# 07_Audio.net
KiCad netlist of a schematic drawn in Altium Designer
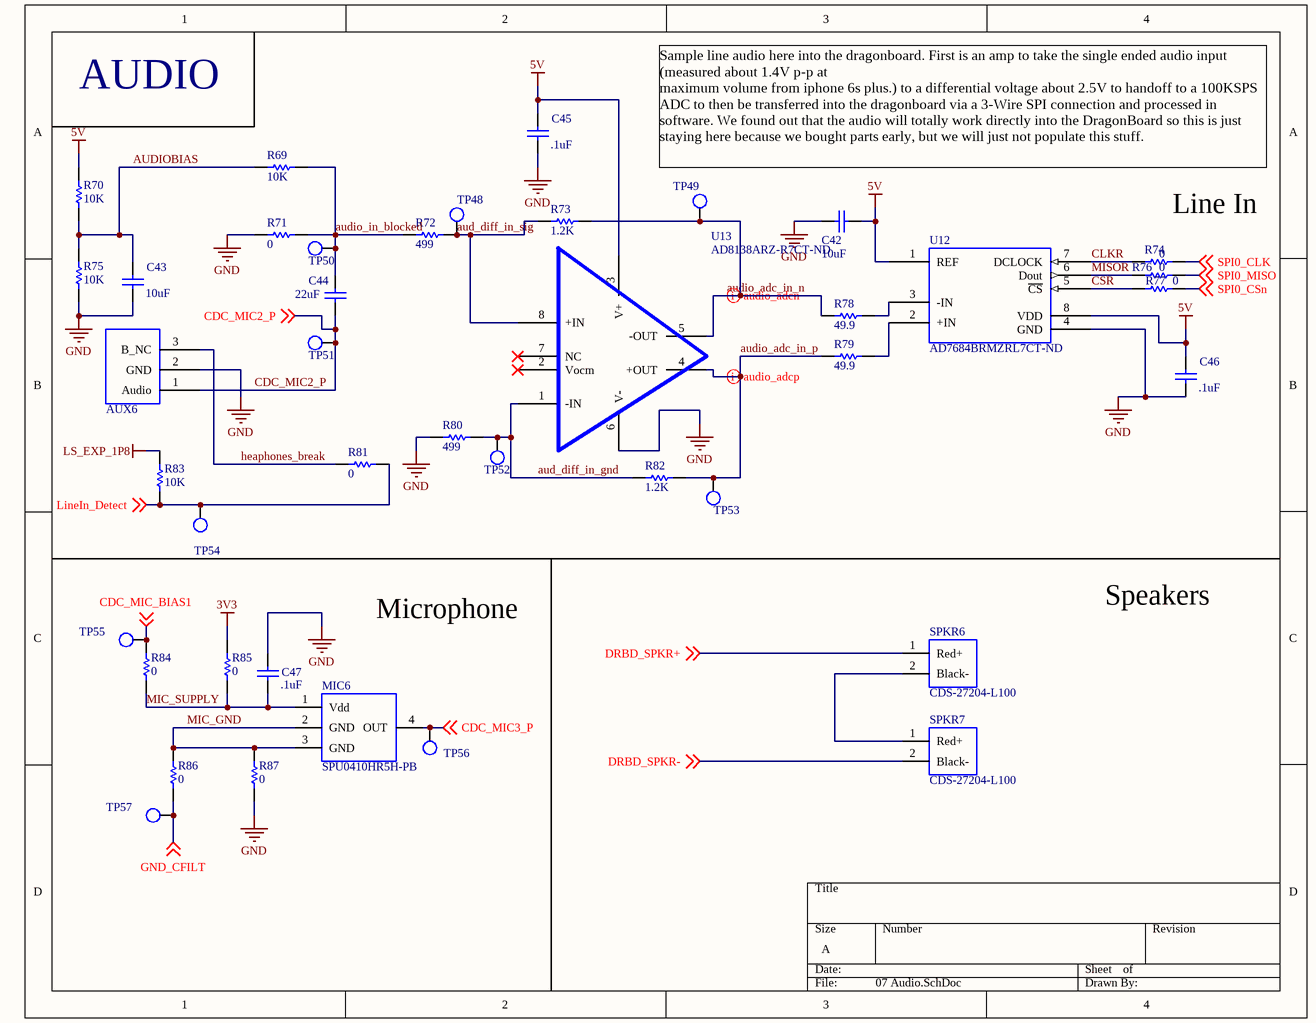
[diagram p0: 07 Audio.SchDoc]

(export (version "E")
  (design (tool "Eeschema 10.0.6"))
  (components
    (comp (ref "AUX6")
      (value "CP-3523MJCT-ND")
      (footprint "Audio_Conn_Mono")
      (description "3.50mm (0.141\", 1/8\", Mini Plug) - Headphone Phone Jack Mono Connector Solder")
      (fields (field (name "MANUFACTURER") "CUI") (field (name "MANUFACTURER PART NUMBER") "MJ-3523-SMT-TR"))
      (libsource (lib "schlib_truman") (part "CP-3523MJCT-ND"))
    )
    (comp (ref "C42")
      (value "10uF")
      (footprint "CAPC2012X135N")
      (description "Cap Ceramic 10uF 16V X5R 10% SMD 0805 85C T/R")
      (fields
        (field (name "MANUFACTURER") "Johanson Dielectrics")
        (field (name "MANUFACTURER PART NUMBER") "160R15X106KV4E")
      )
      (libsource (lib "schlib_truman") (part "CAP_0805_10u_16V"))
    )
    (comp (ref "C43")
      (value "10uF")
      (footprint "CAPC2012X135N")
      (description "Cap Ceramic 10uF 16V X5R 10% SMD 0805 85C T/R")
      (fields
        (field (name "MANUFACTURER") "Johanson Dielectrics")
        (field (name "MANUFACTURER PART NUMBER") "160R15X106KV4E")
      )
      (libsource (lib "schlib_truman") (part "CAP_0805_10u_16V"))
    )
    (comp (ref "C44")
      (value "22uF")
      (footprint "CAPC2012X135N")
      (fields
        (field (name "MANUFACTURER") "Samsung")
        (field (name "MANUFACTURER PART NUMBER") "CL21A226MAQNNNE")
        (field (name "TOLERANCE") "20%")
      )
      (libsource (lib "schlib_truman") (part "CAP_0805_22u_25V_BLOCK"))
    )
    (comp (ref "C45")
      (value ".1uF")
      (footprint "CAPC2012X135N")
      (description "Cap Ceramic 0.1uF 250V X7T 10% SMD 0805 125C Plastic T/R")
      (fields
        (field (name "MANUFACTURER") "TDK")
        (field (name "MANUFACTURER PART NUMBER") "C2012X7T2E104K125AE")
      )
      (libsource (lib "schlib_truman") (part "CAP_0805_.1u_250V"))
    )
    (comp (ref "C46")
      (value ".1uF")
      (footprint "CAPC2012X135N")
      (description "Cap Ceramic 0.1uF 250V X7T 10% SMD 0805 125C Plastic T/R")
      (fields
        (field (name "MANUFACTURER") "TDK")
        (field (name "MANUFACTURER PART NUMBER") "C2012X7T2E104K125AE")
      )
      (libsource (lib "schlib_truman") (part "CAP_0805_.1u_250V"))
    )
    (comp (ref "C47")
      (value ".1uF")
      (footprint "CAPC2012X135N")
      (description "Cap Ceramic 0.1uF 250V X7T 10% SMD 0805 125C Plastic T/R")
      (fields
        (field (name "MANUFACTURER") "TDK")
        (field (name "MANUFACTURER PART NUMBER") "C2012X7T2E104K125AE")
      )
      (libsource (lib "schlib_truman") (part "CAP_0805_.1u_250V"))
    )
    (comp (ref "MIC6")
      (value "SPU0410HR5H-PB")
      (footprint "MIC_FP")
      (description "MIC MEMS ANALOG OMNI -42DB")
      (fields (field (name "MANUFACTURER") "Knowles"))
      (libsource (lib "schlib_truman") (part "SPU0410HR5H-PB"))
    )
    (comp (ref "R69")
      (value "RES_0805_10K")
      (footprint "RES0805")
      (description "RES, THICK FILM, 10K, 5%, 0.125W, 0805")
      (fields
        (field (name "MANUFACTURER") "Yageo")
        (field (name "MANUFACTURER PART NUMBER") "RC0805JR-0710KL")
        (field (name "RESISTANCE") "10K")
      )
      (libsource (lib "schlib_truman") (part "RES_0805_10K"))
    )
    (comp (ref "R70")
      (value "RES_0805_10K")
      (footprint "RES0805")
      (description "RES, THICK FILM, 10K, 5%, 0.125W, 0805")
      (fields
        (field (name "MANUFACTURER") "Yageo")
        (field (name "MANUFACTURER PART NUMBER") "RC0805JR-0710KL")
        (field (name "RESISTANCE") "10K")
      )
      (libsource (lib "schlib_truman") (part "RES_0805_10K"))
    )
    (comp (ref "R71")
      (value "RES_0805_JMP")
      (footprint "RES0805")
      (description "RES, THICK FILM, 0R, 0.125W, 0805")
      (fields
        (field (name "MANUFACTURER") "Yageo")
        (field (name "MANUFACTURER PART NUMBER") "RC0805JR-070RL")
        (field (name "ALTIUM_UNNAMED_1") "0")
      )
      (libsource (lib "schlib_truman") (part "RES_0805_JMP"))
    )
    (comp (ref "R72")
      (value "RES_0805_499")
      (footprint "RES0805")
      (description "Res Thick Film 0805 499 Ohm 1% 0.125W(1/8W) ±100ppm/C Molded SMD Automotive T/R")
      (fields
        (field (name "MANUFACTURER") "Stackpole Electronics")
        (field (name "MANUFACTURER PART NUMBER") "RMCF0805FT499R")
        (field (name "RESISTANCE") "499")
      )
      (libsource (lib "schlib_truman") (part "RES_0805_499"))
    )
    (comp (ref "R73")
      (value "RES_0805_1.2K")
      (footprint "RES0805")
      (description "Res Thick Film 0805 1.2K Ohm 5% 0.125W(1/8W) ±200ppm/C Molded SMD Automotive T/R")
      (fields
        (field (name "MANUFACTURER") "Stackpole Electronics")
        (field (name "MANUFACTURER PART NUMBER") "RMCF0805JT1K20")
        (field (name "RESISTANCE") "1.2K")
      )
      (libsource (lib "schlib_truman") (part "RES_0805_1.2K"))
    )
    (comp (ref "R74")
      (value "RES_0805_JMP")
      (footprint "RES0805")
      (description "RES, THICK FILM, 0R, 0.125W, 0805")
      (fields
        (field (name "MANUFACTURER") "Yageo")
        (field (name "MANUFACTURER PART NUMBER") "RC0805JR-070RL")
        (field (name "ALTIUM_UNNAMED_1") "0")
      )
      (libsource (lib "schlib_truman") (part "RES_0805_JMP"))
    )
    (comp (ref "R75")
      (value "RES_0805_10K")
      (footprint "RES0805")
      (description "RES, THICK FILM, 10K, 5%, 0.125W, 0805")
      (fields
        (field (name "MANUFACTURER") "Yageo")
        (field (name "MANUFACTURER PART NUMBER") "RC0805JR-0710KL")
        (field (name "RESISTANCE") "10K")
      )
      (libsource (lib "schlib_truman") (part "RES_0805_10K"))
    )
    (comp (ref "R76")
      (value "RES_0805_JMP")
      (footprint "RES0805")
      (description "RES, THICK FILM, 0R, 0.125W, 0805")
      (fields
        (field (name "MANUFACTURER") "Yageo")
        (field (name "MANUFACTURER PART NUMBER") "RC0805JR-070RL")
        (field (name "ALTIUM_UNNAMED_1") "0")
      )
      (libsource (lib "schlib_truman") (part "RES_0805_JMP"))
    )
    (comp (ref "R77")
      (value "RES_0805_JMP")
      (footprint "RES0805")
      (description "RES, THICK FILM, 0R, 0.125W, 0805")
      (fields
        (field (name "MANUFACTURER") "Yageo")
        (field (name "MANUFACTURER PART NUMBER") "RC0805JR-070RL")
        (field (name "ALTIUM_UNNAMED_1") "0")
      )
      (libsource (lib "schlib_truman") (part "RES_0805_JMP"))
    )
    (comp (ref "R78")
      (value "RES_0805_49.9")
      (footprint "RES0805")
      (description "RES SMD 49.9 OHM 1% 1/8W 0805")
      (fields
        (field (name "MANUFACTURER") "Yageo")
        (field (name "MANUFACTURER PART NUMBER") "RC0805FR-0749R9L")
        (field (name "RESISTANCE") "49.9")
      )
      (libsource (lib "schlib_truman") (part "RES_0805_49.9"))
    )
    (comp (ref "R79")
      (value "RES_0805_49.9")
      (footprint "RES0805")
      (description "RES SMD 49.9 OHM 1% 1/8W 0805")
      (fields
        (field (name "MANUFACTURER") "Yageo")
        (field (name "MANUFACTURER PART NUMBER") "RC0805FR-0749R9L")
        (field (name "RESISTANCE") "49.9")
      )
      (libsource (lib "schlib_truman") (part "RES_0805_49.9"))
    )
    (comp (ref "R80")
      (value "RES_0805_499")
      (footprint "RES0805")
      (description "Res Thick Film 0805 499 Ohm 1% 0.125W(1/8W) ±100ppm/C Molded SMD Automotive T/R")
      (fields
        (field (name "MANUFACTURER") "Stackpole Electronics")
        (field (name "MANUFACTURER PART NUMBER") "RMCF0805FT499R")
        (field (name "RESISTANCE") "499")
      )
      (libsource (lib "schlib_truman") (part "RES_0805_499"))
    )
    (comp (ref "R81")
      (value "RES_0805_JMP")
      (footprint "RES0805")
      (description "RES, THICK FILM, 0R, 0.125W, 0805")
      (fields
        (field (name "MANUFACTURER") "Yageo")
        (field (name "MANUFACTURER PART NUMBER") "RC0805JR-070RL")
        (field (name "ALTIUM_UNNAMED_1") "0")
      )
      (libsource (lib "schlib_truman") (part "RES_0805_JMP"))
    )
    (comp (ref "R82")
      (value "RES_0805_1.2K")
      (footprint "RES0805")
      (description "Res Thick Film 0805 1.2K Ohm 5% 0.125W(1/8W) ±200ppm/C Molded SMD Automotive T/R")
      (fields
        (field (name "MANUFACTURER") "Stackpole Electronics")
        (field (name "MANUFACTURER PART NUMBER") "RMCF0805JT1K20")
        (field (name "RESISTANCE") "1.2K")
      )
      (libsource (lib "schlib_truman") (part "RES_0805_1.2K"))
    )
    (comp (ref "R83")
      (value "RES_0805_10K")
      (footprint "RES0805")
      (description "RES, THICK FILM, 10K, 5%, 0.125W, 0805")
      (fields
        (field (name "MANUFACTURER") "Yageo")
        (field (name "MANUFACTURER PART NUMBER") "RC0805JR-0710KL")
        (field (name "RESISTANCE") "10K")
      )
      (libsource (lib "schlib_truman") (part "RES_0805_10K"))
    )
    (comp (ref "R84")
      (value "RES_0805_JMP")
      (footprint "RES0805")
      (description "RES, THICK FILM, 0R, 0.125W, 0805")
      (fields
        (field (name "MANUFACTURER") "Yageo")
        (field (name "MANUFACTURER PART NUMBER") "RC0805JR-070RL")
        (field (name "ALTIUM_UNNAMED_1") "0")
      )
      (libsource (lib "schlib_truman") (part "RES_0805_JMP"))
    )
    (comp (ref "R85")
      (value "RES_0805_JMP")
      (footprint "RES0805")
      (description "RES, THICK FILM, 0R, 0.125W, 0805")
      (fields
        (field (name "MANUFACTURER") "Yageo")
        (field (name "MANUFACTURER PART NUMBER") "RC0805JR-070RL")
        (field (name "ALTIUM_UNNAMED_1") "0")
      )
      (libsource (lib "schlib_truman") (part "RES_0805_JMP"))
    )
    (comp (ref "R86")
      (value "RES_0805_JMP")
      (footprint "RES0805")
      (description "RES, THICK FILM, 0R, 0.125W, 0805")
      (fields
        (field (name "MANUFACTURER") "Yageo")
        (field (name "MANUFACTURER PART NUMBER") "RC0805JR-070RL")
        (field (name "ALTIUM_UNNAMED_1") "0")
      )
      (libsource (lib "schlib_truman") (part "RES_0805_JMP"))
    )
    (comp (ref "R87")
      (value "RES_0805_JMP")
      (footprint "RES0805")
      (description "RES, THICK FILM, 0R, 0.125W, 0805")
      (fields
        (field (name "MANUFACTURER") "Yageo")
        (field (name "MANUFACTURER PART NUMBER") "RC0805JR-070RL")
        (field (name "ALTIUM_UNNAMED_1") "0")
      )
      (libsource (lib "schlib_truman") (part "RES_0805_JMP"))
    )
    (comp (ref "SPKR6")
      (value "CDS-27204-L100")
      (footprint "PHOENIX_2POS_1935161")
      (description "4 Ohm Magnetic Speaker 2W 20Hz ~ 20kHz Top Rectangular 93dB")
      (fields (field (name "MANUFACTURER") "CUI") (field (name "VOLTAGE") "300V"))
      (libsource (lib "schlib_truman") (part "CDS-27204-L100"))
    )
    (comp (ref "SPKR7")
      (value "CDS-27204-L100")
      (footprint "PHOENIX_2POS_1935161")
      (description "4 Ohm Magnetic Speaker 2W 20Hz ~ 20kHz Top Rectangular 93dB")
      (fields (field (name "MANUFACTURER") "CUI") (field (name "VOLTAGE") "300V"))
      (libsource (lib "schlib_truman") (part "CDS-27204-L100"))
    )
    (comp (ref "TP48")
      (value "TP")
      (footprint "TestPoint_0805")
      (description "Testpoint_0805")
      (fields
        (field (name "MANUFACTURER") "TE Connectivity")
        (field (name "MANUFACTURER PART NUMBER") "1625854-2")
      )
      (libsource (lib "schlib_truman") (part "TP"))
    )
    (comp (ref "TP49")
      (value "TP")
      (footprint "TestPoint_0805")
      (description "Testpoint_0805")
      (fields
        (field (name "MANUFACTURER") "TE Connectivity")
        (field (name "MANUFACTURER PART NUMBER") "1625854-2")
      )
      (libsource (lib "schlib_truman") (part "TP"))
    )
    (comp (ref "TP50")
      (value "TP")
      (footprint "TestPoint_0805")
      (description "Testpoint_0805")
      (fields
        (field (name "MANUFACTURER") "TE Connectivity")
        (field (name "MANUFACTURER PART NUMBER") "1625854-2")
      )
      (libsource (lib "schlib_truman") (part "TP"))
    )
    (comp (ref "TP51")
      (value "TP")
      (footprint "TestPoint_0805")
      (description "Testpoint_0805")
      (fields
        (field (name "MANUFACTURER") "TE Connectivity")
        (field (name "MANUFACTURER PART NUMBER") "1625854-2")
      )
      (libsource (lib "schlib_truman") (part "TP"))
    )
    (comp (ref "TP52")
      (value "TP")
      (footprint "TestPoint_0805")
      (description "Testpoint_0805")
      (fields
        (field (name "MANUFACTURER") "TE Connectivity")
        (field (name "MANUFACTURER PART NUMBER") "1625854-2")
      )
      (libsource (lib "schlib_truman") (part "TP"))
    )
    (comp (ref "TP53")
      (value "TP")
      (footprint "TestPoint_0805")
      (description "Testpoint_0805")
      (fields
        (field (name "MANUFACTURER") "TE Connectivity")
        (field (name "MANUFACTURER PART NUMBER") "1625854-2")
      )
      (libsource (lib "schlib_truman") (part "TP"))
    )
    (comp (ref "TP54")
      (value "TP")
      (footprint "TestPoint_0805")
      (description "Testpoint_0805")
      (fields
        (field (name "MANUFACTURER") "TE Connectivity")
        (field (name "MANUFACTURER PART NUMBER") "1625854-2")
      )
      (libsource (lib "schlib_truman") (part "TP"))
    )
    (comp (ref "TP55")
      (value "TP")
      (footprint "TestPoint_0805")
      (description "Testpoint_0805")
      (fields
        (field (name "MANUFACTURER") "TE Connectivity")
        (field (name "MANUFACTURER PART NUMBER") "1625854-2")
      )
      (libsource (lib "schlib_truman") (part "TP"))
    )
    (comp (ref "TP56")
      (value "TP")
      (footprint "TestPoint_0805")
      (description "Testpoint_0805")
      (fields
        (field (name "MANUFACTURER") "TE Connectivity")
        (field (name "MANUFACTURER PART NUMBER") "1625854-2")
      )
      (libsource (lib "schlib_truman") (part "TP"))
    )
    (comp (ref "TP57")
      (value "TP")
      (footprint "TestPoint_0805")
      (description "Testpoint_0805")
      (fields
        (field (name "MANUFACTURER") "TE Connectivity")
        (field (name "MANUFACTURER PART NUMBER") "1625854-2")
      )
      (libsource (lib "schlib_truman") (part "TP"))
    )
    (comp (ref "U12")
      (value "AD7684BRMZRL7CT-ND")
      (footprint "MSOP8")
      (description "IC ADC 16BIT 100KSPS DIFF 8MSOP")
      (fields
        (field (name "MANUFACTURER") "Analog Devices")
        (field (name "MANUFACTURER PART NUMBER") "AD7684BRMZRL7")
      )
      (libsource (lib "schlib_truman") (part "AD7684BRMZRL7CT-ND"))
    )
    (comp (ref "U13")
      (value "AD8138ARZ-R7CT-ND")
      (footprint "SOIC127P600X175-8N")
      (description "SP Amp Differential ADC Driver Single ±5.5V/11V 8-Pin SOIC N T/R")
      (fields
        (field (name "MANUFACTURER") "Analog Devices")
        (field (name "MANUFACTURER PART NUMBER") "AD8138ARZ-R7")
      )
      (libsource (lib "schlib_truman") (part "AD8138ARZ-R7CT-ND"))
    )
  )
  (nets
    (net (code "1") (name "/AUDIOBIAS") (class "Default")
      (node (ref "C43") (pin "2") (pinfunction "2_2") (pintype "passive"))
      (node (ref "R69") (pin "1") (pinfunction "1_1") (pintype "passive"))
      (node (ref "R70") (pin "1") (pinfunction "1_1") (pintype "passive"))
      (node (ref "R75") (pin "2") (pinfunction "2_2") (pintype "passive"))
    )
    (net (code "2") (name "/CLKR") (class "Default")
      (node (ref "R74") (pin "1") (pinfunction "1_1") (pintype "passive"))
      (node (ref "U12") (pin "7") (pinfunction "DCLOCK_7") (pintype "input"))
    )
    (net (code "3") (name "/CSR") (class "Default")
      (node (ref "R77") (pin "1") (pinfunction "1_1") (pintype "passive"))
      (node (ref "U12") (pin "5") (pinfunction "~{CS}_5") (pintype "input"))
    )
    (net (code "4") (name "/MIC_GND") (class "Default")
      (node (ref "MIC6") (pin "2") (pinfunction "GND_2") (pintype "passive"))
      (node (ref "MIC6") (pin "3") (pinfunction "GND_3") (pintype "passive"))
      (node (ref "R86") (pin "2") (pinfunction "2_2") (pintype "passive"))
      (node (ref "R87") (pin "2") (pinfunction "2_2") (pintype "passive"))
    )
    (net (code "5") (name "/MIC_SUPPLY") (class "Default")
      (node (ref "C47") (pin "1") (pinfunction "1_1") (pintype "passive"))
      (node (ref "MIC6") (pin "1") (pinfunction "Vdd_1") (pintype "passive"))
      (node (ref "R84") (pin "1") (pinfunction "1_1") (pintype "passive"))
      (node (ref "R85") (pin "1") (pinfunction "1_1") (pintype "passive"))
    )
    (net (code "6") (name "/MISOR") (class "Default")
      (node (ref "R76") (pin "1") (pinfunction "1_1") (pintype "passive"))
      (node (ref "U12") (pin "6") (pinfunction "Dout_6") (pintype "output"))
    )
    (net (code "7") (name "/aud_diff_in_gnd") (class "Default")
      (node (ref "R80") (pin "2") (pinfunction "2_2") (pintype "passive"))
      (node (ref "R82") (pin "1") (pinfunction "1_1") (pintype "passive"))
      (node (ref "TP52") (pin "1") (pintype "passive"))
      (node (ref "U13") (pin "1") (pinfunction "-IN_1") (pintype "passive"))
    )
    (net (code "8") (name "/aud_diff_in_sig") (class "Default")
      (node (ref "R72") (pin "2") (pinfunction "2_2") (pintype "passive"))
      (node (ref "R73") (pin "1") (pinfunction "1_1") (pintype "passive"))
      (node (ref "TP48") (pin "1") (pintype "passive"))
      (node (ref "U13") (pin "8") (pinfunction "+IN_8") (pintype "passive"))
    )
    (net (code "9") (name "/audio_adc_in_n") (class "Default")
      (node (ref "R73") (pin "2") (pinfunction "2_2") (pintype "passive"))
      (node (ref "R78") (pin "1") (pinfunction "1_1") (pintype "passive"))
      (node (ref "TP49") (pin "1") (pintype "passive"))
      (node (ref "U13") (pin "5") (pinfunction "-OUT_5") (pintype "passive"))
    )
    (net (code "10") (name "/audio_adc_in_p") (class "Default")
      (node (ref "R79") (pin "1") (pinfunction "1_1") (pintype "passive"))
      (node (ref "R82") (pin "2") (pinfunction "2_2") (pintype "passive"))
      (node (ref "TP53") (pin "1") (pintype "passive"))
      (node (ref "U13") (pin "4") (pinfunction "+OUT_4") (pintype "passive"))
    )
    (net (code "11") (name "/audio_in_blocked") (class "Default")
      (node (ref "C44") (pin "2") (pinfunction "2_2") (pintype "passive"))
      (node (ref "R69") (pin "2") (pinfunction "2_2") (pintype "passive"))
      (node (ref "R71") (pin "2") (pinfunction "2_2") (pintype "passive"))
      (node (ref "R72") (pin "1") (pinfunction "1_1") (pintype "passive"))
      (node (ref "TP50") (pin "1") (pintype "passive"))
    )
    (net (code "12") (name "/heaphones_break") (class "Default")
      (node (ref "AUX6") (pin "3") (pinfunction "B_NC_3") (pintype "passive"))
      (node (ref "R81") (pin "1") (pinfunction "1_1") (pintype "passive"))
    )
    (net (code "13") (name "3V3") (class "Default")
      (node (ref "R85") (pin "2") (pinfunction "2_2") (pintype "passive"))
    )
    (net (code "14") (name "5V") (class "Default")
      (node (ref "C42") (pin "1") (pinfunction "1_1") (pintype "passive"))
      (node (ref "C45") (pin "2") (pinfunction "2_2") (pintype "passive"))
      (node (ref "C46") (pin "2") (pinfunction "2_2") (pintype "passive"))
      (node (ref "R70") (pin "2") (pinfunction "2_2") (pintype "passive"))
      (node (ref "U12") (pin "1") (pinfunction "REF_1") (pintype "passive"))
      (node (ref "U12") (pin "8") (pinfunction "VDD_8") (pintype "passive"))
      (node (ref "U13") (pin "3") (pinfunction "V+_3") (pintype "passive"))
    )
    (net (code "15") (name "CDC_MIC2_P") (class "Default")
      (node (ref "AUX6") (pin "1") (pinfunction "Audio_1") (pintype "passive"))
      (node (ref "C44") (pin "1") (pinfunction "1_1") (pintype "passive"))
      (node (ref "TP51") (pin "1") (pintype "passive"))
    )
    (net (code "16") (name "CDC_MIC3_P") (class "Default")
      (node (ref "MIC6") (pin "4") (pinfunction "OUT_4") (pintype "passive"))
      (node (ref "TP56") (pin "1") (pintype "passive"))
    )
    (net (code "17") (name "CDC_MIC_BIAS1") (class "Default")
      (node (ref "R84") (pin "2") (pinfunction "2_2") (pintype "passive"))
      (node (ref "TP55") (pin "1") (pintype "passive"))
    )
    (net (code "18") (name "DRBD_SPKR+") (class "Default")
      (node (ref "SPKR6") (pin "1") (pinfunction "Red+_1") (pintype "passive"))
    )
    (net (code "19") (name "DRBD_SPKR-") (class "Default")
      (node (ref "SPKR7") (pin "2") (pinfunction "Black-_2") (pintype "passive"))
    )
    (net (code "20") (name "GND") (class "Default")
      (node (ref "AUX6") (pin "2") (pinfunction "GND_2") (pintype "passive"))
      (node (ref "C42") (pin "2") (pinfunction "2_2") (pintype "passive"))
      (node (ref "C43") (pin "1") (pinfunction "1_1") (pintype "passive"))
      (node (ref "C45") (pin "1") (pinfunction "1_1") (pintype "passive"))
      (node (ref "C46") (pin "1") (pinfunction "1_1") (pintype "passive"))
      (node (ref "C47") (pin "2") (pinfunction "2_2") (pintype "passive"))
      (node (ref "R71") (pin "1") (pinfunction "1_1") (pintype "passive"))
      (node (ref "R75") (pin "1") (pinfunction "1_1") (pintype "passive"))
      (node (ref "R80") (pin "1") (pinfunction "1_1") (pintype "passive"))
      (node (ref "R87") (pin "1") (pinfunction "1_1") (pintype "passive"))
      (node (ref "U12") (pin "4") (pinfunction "GND_4") (pintype "passive"))
      (node (ref "U13") (pin "6") (pinfunction "V-_6") (pintype "passive"))
    )
    (net (code "21") (name "GND_CFILT") (class "Default")
      (node (ref "R86") (pin "1") (pinfunction "1_1") (pintype "passive"))
      (node (ref "TP57") (pin "1") (pintype "passive"))
    )
    (net (code "22") (name "LS_EXP_1P8") (class "Default")
      (node (ref "R83") (pin "2") (pinfunction "2_2") (pintype "passive"))
    )
    (net (code "23") (name "LineIn_Detect") (class "Default")
      (node (ref "R81") (pin "2") (pinfunction "2_2") (pintype "passive"))
      (node (ref "R83") (pin "1") (pinfunction "1_1") (pintype "passive"))
      (node (ref "TP54") (pin "1") (pintype "passive"))
    )
    (net (code "24") (name "Net-(SPKR6-Black-)") (class "Default")
      (node (ref "SPKR6") (pin "2") (pinfunction "Black-_2") (pintype "passive"))
      (node (ref "SPKR7") (pin "1") (pinfunction "Red+_1") (pintype "passive"))
    )
    (net (code "25") (name "Net-(U12-+IN)") (class "Default")
      (node (ref "R79") (pin "2") (pinfunction "2_2") (pintype "passive"))
      (node (ref "U12") (pin "2") (pinfunction "+IN_2") (pintype "passive"))
    )
    (net (code "26") (name "Net-(U12--IN)") (class "Default")
      (node (ref "R78") (pin "2") (pinfunction "2_2") (pintype "passive"))
      (node (ref "U12") (pin "3") (pinfunction "-IN_3") (pintype "passive"))
    )
    (net (code "27") (name "SPI0_CLK") (class "Default")
      (node (ref "R74") (pin "2") (pinfunction "2_2") (pintype "passive"))
    )
    (net (code "28") (name "SPI0_CSn") (class "Default")
      (node (ref "R77") (pin "2") (pinfunction "2_2") (pintype "passive"))
    )
    (net (code "29") (name "SPI0_MISO") (class "Default")
      (node (ref "R76") (pin "2") (pinfunction "2_2") (pintype "passive"))
    )
    (net (code "30") (name "unconnected-(U13-NC-Pad7)") (class "Default")
      (node (ref "U13") (pin "7") (pinfunction "NC_7") (pintype "passive+no_connect"))
    )
    (net (code "31") (name "unconnected-(U13-Vocm-Pad2)") (class "Default")
      (node (ref "U13") (pin "2") (pinfunction "Vocm_2") (pintype "passive+no_connect"))
    )
  )
)
